# nRF7002-DK.net
KiCad netlist of a schematic drawn in Altium Designer
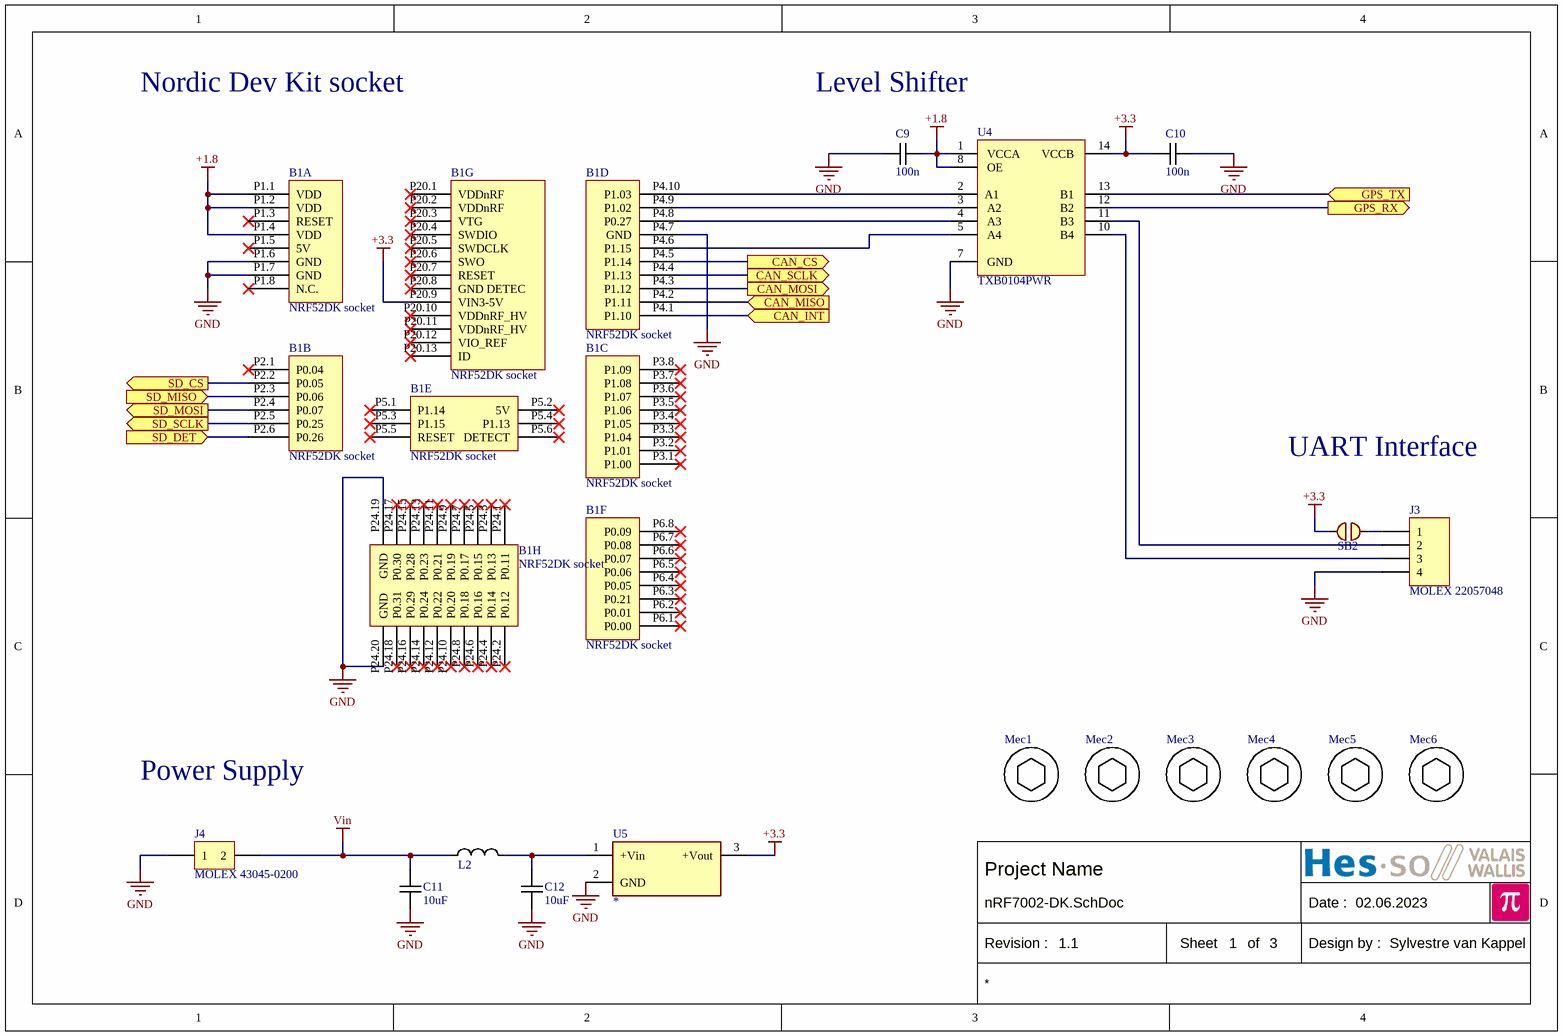
[diagram p0: nRF7002-DK.SchDoc]

(export (version "E")
  (design (tool "Eeschema 10.0.6"))
  (components
    (comp (ref "B1")
      (value "NRF52DK socket")
      (footprint "nRF5340DK SOCKET")
      (description "nRF53 development kit")
      (libsource (lib "") (part "nRF5340DK Socket_1"))
    )
    (comp (ref "C9")
      (value "100n")
      (footprint "CAPACITOR 1608 REFLOW")
      (description "Capacitor")
      (libsource (lib "Capacitor") (part "Capacitor"))
    )
    (comp (ref "C10")
      (value "100n")
      (footprint "CAPACITOR 1608 REFLOW")
      (description "Capacitor")
      (libsource (lib "Capacitor") (part "Capacitor"))
    )
    (comp (ref "C11")
      (value "10uF")
      (footprint "CAPACITOR 3216 REFLOW")
      (description "Capacitor")
      (libsource (lib "Capacitor") (part "Capacitor"))
    )
    (comp (ref "C12")
      (value "10uF")
      (footprint "CAPACITOR 3216 REFLOW")
      (description "Capacitor")
      (libsource (lib "Capacitor") (part "Capacitor"))
    )
    (comp (ref "J3")
      (value "MOLEX 22057048")
      (footprint "MOLEX 22057048")
      (description "KK 254 Wire-to-Board Header, Right-Angle, 4 Circuits")
      (libsource (lib "Connector") (part "MOLEX 22057048"))
    )
    (comp (ref "J4")
      (value "MOLEX 43045-0200")
      (footprint "MOLEX 43045-0200")
      (description "Micro-Fit 3.0 Right-Angle Header, 3.00mm, Dual Row, 2 Circuits")
      (libsource (lib "Connector") (part "MOLEX 43045-0200"))
    )
    (comp (ref "L2")
      (value "*")
      (footprint "TCK141")
      (description "Inductor")
      (libsource (lib "Inductor") (part "Inductor"))
    )
    (comp (ref "Mec1")
      (value "~")
      (footprint "Screw Hex Socket M3X5 Unconnected")
      (description "Screw Hex Socket Unconnected BN610")
      (libsource (lib "Mechanic") (part "Screw Hex Socket Unconnected"))
    )
    (comp (ref "Mec2")
      (value "~")
      (footprint "Screw Hex Socket M3X5 Unconnected")
      (description "Screw Hex Socket Unconnected BN610")
      (libsource (lib "Mechanic") (part "Screw Hex Socket Unconnected"))
    )
    (comp (ref "Mec3")
      (value "~")
      (footprint "Screw Hex Socket M3X5 Unconnected")
      (description "Screw Hex Socket Unconnected BN610")
      (libsource (lib "Mechanic") (part "Screw Hex Socket Unconnected"))
    )
    (comp (ref "Mec4")
      (value "~")
      (footprint "Screw Hex Socket M3X5 Unconnected")
      (description "Screw Hex Socket Unconnected BN610")
      (libsource (lib "Mechanic") (part "Screw Hex Socket Unconnected"))
    )
    (comp (ref "Mec5")
      (value "~")
      (footprint "Screw Hex Socket M3X5 Unconnected")
      (description "Screw Hex Socket Unconnected BN610")
      (libsource (lib "Mechanic") (part "Screw Hex Socket Unconnected"))
    )
    (comp (ref "Mec6")
      (value "~")
      (footprint "Screw Hex Socket M3X5 Unconnected")
      (description "Screw Hex Socket Unconnected BN610")
      (libsource (lib "Mechanic") (part "Screw Hex Socket Unconnected"))
    )
    (comp (ref "SB2")
      (value "*")
      (footprint "Solder Bridge 1mm Unconnected")
      (description "Solderbridge Unconnected")
      (libsource (lib "Jumper") (part "Solderbridge Unconnected"))
    )
    (comp (ref "U4")
      (value "TXB0104PWR")
      (footprint "TSSOP14 P0.65 C4.4x5.0 H1.1")
      (libsource (lib "IntegratedCircuit") (part "TXB0104PWR"))
    )
    (comp (ref "U5")
      (value "*")
      (footprint "TRACO TSR 1")
      (description "DC/DC Converter")
      (libsource (lib "VoltageConverter") (part "TRACO TSR 1"))
    )
  )
  (nets
    (net (code "1") (name "+1.8") (class "Default")
      (node (ref "B1") (pin "P1.1") (pinfunction "VDD_P1.1") (pintype "passive"))
      (node (ref "B1") (pin "P1.2") (pinfunction "VDD_P1.2") (pintype "passive"))
      (node (ref "B1") (pin "P1.4") (pinfunction "VDD_P1.4") (pintype "passive"))
      (node (ref "C9") (pin "1") (pinfunction "1_1") (pintype "passive"))
      (node (ref "U4") (pin "1") (pinfunction "VCCA_1") (pintype "passive"))
      (node (ref "U4") (pin "8") (pinfunction "OE_8") (pintype "passive"))
    )
    (net (code "2") (name "+3.3") (class "Default")
      (node (ref "B1") (pin "P20.9") (pinfunction "VIN3-5V_P20.9") (pintype "passive"))
      (node (ref "C10") (pin "2") (pinfunction "2_2") (pintype "passive"))
      (node (ref "SB2") (pin "2") (pinfunction "1_2") (pintype "passive"))
      (node (ref "U4") (pin "14") (pinfunction "VCCB_14") (pintype "passive"))
      (node (ref "U5") (pin "3") (pinfunction "+Vout_3") (pintype "passive"))
    )
    (net (code "3") (name "/CAN_CS") (class "Default")
      (node (ref "B1") (pin "P4.5") (pinfunction "P1.14_P4.5") (pintype "passive"))
    )
    (net (code "4") (name "/CAN_INT") (class "Default")
      (node (ref "B1") (pin "P4.1") (pinfunction "P1.10_P4.1") (pintype "passive"))
    )
    (net (code "5") (name "/CAN_MISO") (class "Default")
      (node (ref "B1") (pin "P4.2") (pinfunction "P1.11_P4.2") (pintype "passive"))
    )
    (net (code "6") (name "/CAN_MOSI") (class "Default")
      (node (ref "B1") (pin "P4.3") (pinfunction "P1.12_P4.3") (pintype "passive"))
    )
    (net (code "7") (name "/CAN_SCLK") (class "Default")
      (node (ref "B1") (pin "P4.4") (pinfunction "P1.13_P4.4") (pintype "passive"))
    )
    (net (code "8") (name "/GPS_RX") (class "Default")
      (node (ref "U4") (pin "12") (pinfunction "B2_12") (pintype "passive"))
    )
    (net (code "9") (name "/GPS_TX") (class "Default")
      (node (ref "U4") (pin "13") (pinfunction "B1_13") (pintype "passive"))
    )
    (net (code "10") (name "/SD_CS") (class "Default")
      (node (ref "B1") (pin "P2.2") (pinfunction "P0.05_P2.2") (pintype "passive"))
    )
    (net (code "11") (name "/SD_DET") (class "Default")
      (node (ref "B1") (pin "P2.6") (pinfunction "P0.26_P2.6") (pintype "passive"))
    )
    (net (code "12") (name "/SD_MISO") (class "Default")
      (node (ref "B1") (pin "P2.3") (pinfunction "P0.06_P2.3") (pintype "passive"))
    )
    (net (code "13") (name "/SD_MOSI") (class "Default")
      (node (ref "B1") (pin "P2.4") (pinfunction "P0.07_P2.4") (pintype "passive"))
    )
    (net (code "14") (name "/SD_SCLK") (class "Default")
      (node (ref "B1") (pin "P2.5") (pinfunction "P0.25_P2.5") (pintype "passive"))
    )
    (net (code "15") (name "GND") (class "Default")
      (node (ref "B1") (pin "P1.6") (pinfunction "GND_P1.6") (pintype "passive"))
      (node (ref "B1") (pin "P1.7") (pinfunction "GND_P1.7") (pintype "passive"))
      (node (ref "B1") (pin "P24.19") (pinfunction "GND_P24.19") (pintype "passive"))
      (node (ref "B1") (pin "P24.20") (pinfunction "GND_P24.20") (pintype "passive"))
      (node (ref "B1") (pin "P4.7") (pinfunction "GND_P4.7") (pintype "passive"))
      (node (ref "C10") (pin "1") (pinfunction "1_1") (pintype "passive"))
      (node (ref "C11") (pin "2") (pinfunction "2_2") (pintype "passive"))
      (node (ref "C12") (pin "2") (pinfunction "2_2") (pintype "passive"))
      (node (ref "C9") (pin "2") (pinfunction "2_2") (pintype "passive"))
      (node (ref "J3") (pin "4") (pinfunction "4_4") (pintype "passive"))
      (node (ref "J4") (pin "1") (pinfunction "1_1") (pintype "passive"))
      (node (ref "U4") (pin "7") (pinfunction "GND_7") (pintype "passive"))
      (node (ref "U5") (pin "2") (pinfunction "GND_2") (pintype "passive"))
    )
    (net (code "16") (name "Net-(B1D-P0.27)") (class "Default")
      (node (ref "B1") (pin "P4.8") (pinfunction "P0.27_P4.8") (pintype "passive"))
      (node (ref "U4") (pin "4") (pinfunction "A3_4") (pintype "passive"))
    )
    (net (code "17") (name "Net-(B1D-P1.02)") (class "Default")
      (node (ref "B1") (pin "P4.9") (pinfunction "P1.02_P4.9") (pintype "passive"))
      (node (ref "U4") (pin "3") (pinfunction "A2_3") (pintype "passive"))
    )
    (net (code "18") (name "Net-(B1D-P1.03)") (class "Default")
      (node (ref "B1") (pin "P4.10") (pinfunction "P1.03_P4.10") (pintype "passive"))
      (node (ref "U4") (pin "2") (pinfunction "A1_2") (pintype "passive"))
    )
    (net (code "19") (name "Net-(B1D-P1.15)") (class "Default")
      (node (ref "B1") (pin "P4.6") (pinfunction "P1.15_P4.6") (pintype "passive"))
      (node (ref "U4") (pin "5") (pinfunction "A4_5") (pintype "passive"))
    )
    (net (code "20") (name "Net-(SB2-0)") (class "Default")
      (node (ref "J3") (pin "1") (pinfunction "1_1") (pintype "passive"))
      (node (ref "SB2") (pin "1") (pinfunction "0_1") (pintype "passive"))
    )
    (net (code "21") (name "Net-(U4-B3)") (class "Default")
      (node (ref "J3") (pin "2") (pinfunction "2_2") (pintype "passive"))
      (node (ref "U4") (pin "11") (pinfunction "B3_11") (pintype "passive"))
    )
    (net (code "22") (name "Net-(U4-B4)") (class "Default")
      (node (ref "J3") (pin "3") (pinfunction "3_3") (pintype "passive"))
      (node (ref "U4") (pin "10") (pinfunction "B4_10") (pintype "passive"))
    )
    (net (code "23") (name "Net-(U5-+Vin)") (class "Default")
      (node (ref "C12") (pin "1") (pinfunction "1_1") (pintype "passive"))
      (node (ref "L2") (pin "2") (pinfunction "2_2") (pintype "passive"))
      (node (ref "U5") (pin "1") (pinfunction "+Vin_1") (pintype "passive"))
    )
    (net (code "24") (name "Vin") (class "Default")
      (node (ref "C11") (pin "1") (pinfunction "1_1") (pintype "passive"))
      (node (ref "J4") (pin "2") (pinfunction "2_2") (pintype "passive"))
      (node (ref "L2") (pin "1") (pinfunction "1_1") (pintype "passive"))
    )
    (net (code "25") (name "unconnected-(B1A-5V-PadP1.5)") (class "Default")
      (node (ref "B1") (pin "P1.5") (pinfunction "5V_P1.5") (pintype "passive+no_connect"))
    )
    (net (code "26") (name "unconnected-(B1A-N.C.-PadP1.8)") (class "Default")
      (node (ref "B1") (pin "P1.8") (pinfunction "N.C._P1.8") (pintype "passive+no_connect"))
    )
    (net (code "27") (name "unconnected-(B1A-RESET-PadP1.3)") (class "Default")
      (node (ref "B1") (pin "P1.3") (pinfunction "RESET_P1.3") (pintype "passive+no_connect"))
    )
    (net (code "28") (name "unconnected-(B1B-P0.04-PadP2.1)") (class "Default")
      (node (ref "B1") (pin "P2.1") (pinfunction "P0.04_P2.1") (pintype "passive+no_connect"))
    )
    (net (code "29") (name "unconnected-(B1C-P1.00-PadP3.1)") (class "Default")
      (node (ref "B1") (pin "P3.1") (pinfunction "P1.00_P3.1") (pintype "passive+no_connect"))
    )
    (net (code "30") (name "unconnected-(B1C-P1.01-PadP3.2)") (class "Default")
      (node (ref "B1") (pin "P3.2") (pinfunction "P1.01_P3.2") (pintype "passive+no_connect"))
    )
    (net (code "31") (name "unconnected-(B1C-P1.04-PadP3.3)") (class "Default")
      (node (ref "B1") (pin "P3.3") (pinfunction "P1.04_P3.3") (pintype "passive+no_connect"))
    )
    (net (code "32") (name "unconnected-(B1C-P1.05-PadP3.4)") (class "Default")
      (node (ref "B1") (pin "P3.4") (pinfunction "P1.05_P3.4") (pintype "passive+no_connect"))
    )
    (net (code "33") (name "unconnected-(B1C-P1.06-PadP3.5)") (class "Default")
      (node (ref "B1") (pin "P3.5") (pinfunction "P1.06_P3.5") (pintype "passive+no_connect"))
    )
    (net (code "34") (name "unconnected-(B1C-P1.07-PadP3.6)") (class "Default")
      (node (ref "B1") (pin "P3.6") (pinfunction "P1.07_P3.6") (pintype "passive+no_connect"))
    )
    (net (code "35") (name "unconnected-(B1C-P1.08-PadP3.7)") (class "Default")
      (node (ref "B1") (pin "P3.7") (pinfunction "P1.08_P3.7") (pintype "passive+no_connect"))
    )
    (net (code "36") (name "unconnected-(B1C-P1.09-PadP3.8)") (class "Default")
      (node (ref "B1") (pin "P3.8") (pinfunction "P1.09_P3.8") (pintype "passive+no_connect"))
    )
    (net (code "37") (name "unconnected-(B1E-5V-PadP5.2)") (class "Default")
      (node (ref "B1") (pin "P5.2") (pinfunction "5V_P5.2") (pintype "passive+no_connect"))
    )
    (net (code "38") (name "unconnected-(B1E-DETECT-PadP5.6)") (class "Default")
      (node (ref "B1") (pin "P5.6") (pinfunction "DETECT_P5.6") (pintype "passive+no_connect"))
    )
    (net (code "39") (name "unconnected-(B1E-P1.13-PadP5.4)") (class "Default")
      (node (ref "B1") (pin "P5.4") (pinfunction "P1.13_P5.4") (pintype "passive+no_connect"))
    )
    (net (code "40") (name "unconnected-(B1E-P1.14-PadP5.1)") (class "Default")
      (node (ref "B1") (pin "P5.1") (pinfunction "P1.14_P5.1") (pintype "passive+no_connect"))
    )
    (net (code "41") (name "unconnected-(B1E-P1.15-PadP5.3)") (class "Default")
      (node (ref "B1") (pin "P5.3") (pinfunction "P1.15_P5.3") (pintype "passive+no_connect"))
    )
    (net (code "42") (name "unconnected-(B1E-RESET-PadP5.5)") (class "Default")
      (node (ref "B1") (pin "P5.5") (pinfunction "RESET_P5.5") (pintype "passive+no_connect"))
    )
    (net (code "43") (name "unconnected-(B1F-P0.00-PadP6.1)") (class "Default")
      (node (ref "B1") (pin "P6.1") (pinfunction "P0.00_P6.1") (pintype "passive+no_connect"))
    )
    (net (code "44") (name "unconnected-(B1F-P0.01-PadP6.2)") (class "Default")
      (node (ref "B1") (pin "P6.2") (pinfunction "P0.01_P6.2") (pintype "passive+no_connect"))
    )
    (net (code "45") (name "unconnected-(B1F-P0.05-PadP6.4)") (class "Default")
      (node (ref "B1") (pin "P6.4") (pinfunction "P0.05_P6.4") (pintype "passive+no_connect"))
    )
    (net (code "46") (name "unconnected-(B1F-P0.06-PadP6.5)") (class "Default")
      (node (ref "B1") (pin "P6.5") (pinfunction "P0.06_P6.5") (pintype "passive+no_connect"))
    )
    (net (code "47") (name "unconnected-(B1F-P0.07-PadP6.6)") (class "Default")
      (node (ref "B1") (pin "P6.6") (pinfunction "P0.07_P6.6") (pintype "passive+no_connect"))
    )
    (net (code "48") (name "unconnected-(B1F-P0.08-PadP6.7)") (class "Default")
      (node (ref "B1") (pin "P6.7") (pinfunction "P0.08_P6.7") (pintype "passive+no_connect"))
    )
    (net (code "49") (name "unconnected-(B1F-P0.09-PadP6.8)") (class "Default")
      (node (ref "B1") (pin "P6.8") (pinfunction "P0.09_P6.8") (pintype "passive+no_connect"))
    )
    (net (code "50") (name "unconnected-(B1F-P0.21-PadP6.3)") (class "Default")
      (node (ref "B1") (pin "P6.3") (pinfunction "P0.21_P6.3") (pintype "passive+no_connect"))
    )
    (net (code "51") (name "unconnected-(B1G-GND_DETEC-PadP20.8)") (class "Default")
      (node (ref "B1") (pin "P20.8") (pinfunction "GND_DETEC_P20.8") (pintype "passive+no_connect"))
    )
    (net (code "52") (name "unconnected-(B1G-ID-PadP20.13)") (class "Default")
      (node (ref "B1") (pin "P20.13") (pinfunction "ID_P20.13") (pintype "passive+no_connect"))
    )
    (net (code "53") (name "unconnected-(B1G-RESET-PadP20.7)") (class "Default")
      (node (ref "B1") (pin "P20.7") (pinfunction "RESET_P20.7") (pintype "passive+no_connect"))
    )
    (net (code "54") (name "unconnected-(B1G-SWDCLK-PadP20.5)") (class "Default")
      (node (ref "B1") (pin "P20.5") (pinfunction "SWDCLK_P20.5") (pintype "passive+no_connect"))
    )
    (net (code "55") (name "unconnected-(B1G-SWDIO-PadP20.4)") (class "Default")
      (node (ref "B1") (pin "P20.4") (pinfunction "SWDIO_P20.4") (pintype "passive+no_connect"))
    )
    (net (code "56") (name "unconnected-(B1G-SWO-PadP20.6)") (class "Default")
      (node (ref "B1") (pin "P20.6") (pinfunction "SWO_P20.6") (pintype "passive+no_connect"))
    )
    (net (code "57") (name "unconnected-(B1G-VDDnRF-PadP20.1)") (class "Default")
      (node (ref "B1") (pin "P20.1") (pinfunction "VDDnRF_P20.1") (pintype "passive+no_connect"))
    )
    (net (code "58") (name "unconnected-(B1G-VDDnRF-PadP20.2)") (class "Default")
      (node (ref "B1") (pin "P20.2") (pinfunction "VDDnRF_P20.2") (pintype "passive+no_connect"))
    )
    (net (code "59") (name "unconnected-(B1G-VDDnRF_HV-PadP20.10)") (class "Default")
      (node (ref "B1") (pin "P20.10") (pinfunction "VDDnRF_HV_P20.10") (pintype "passive+no_connect"))
    )
    (net (code "60") (name "unconnected-(B1G-VDDnRF_HV-PadP20.11)") (class "Default")
      (node (ref "B1") (pin "P20.11") (pinfunction "VDDnRF_HV_P20.11") (pintype "passive+no_connect"))
    )
    (net (code "61") (name "unconnected-(B1G-VIO_REF-PadP20.12)") (class "Default")
      (node (ref "B1") (pin "P20.12") (pinfunction "VIO_REF_P20.12") (pintype "passive+no_connect"))
    )
    (net (code "62") (name "unconnected-(B1G-VTG-PadP20.3)") (class "Default")
      (node (ref "B1") (pin "P20.3") (pinfunction "VTG_P20.3") (pintype "passive+no_connect"))
    )
    (net (code "63") (name "unconnected-(B1H-P0.11-PadP24.1)") (class "Default")
      (node (ref "B1") (pin "P24.1") (pinfunction "P0.11_P24.1") (pintype "passive+no_connect"))
    )
    (net (code "64") (name "unconnected-(B1H-P0.12-PadP24.2)") (class "Default")
      (node (ref "B1") (pin "P24.2") (pinfunction "P0.12_P24.2") (pintype "passive+no_connect"))
    )
    (net (code "65") (name "unconnected-(B1H-P0.13-PadP24.3)") (class "Default")
      (node (ref "B1") (pin "P24.3") (pinfunction "P0.13_P24.3") (pintype "passive+no_connect"))
    )
    (net (code "66") (name "unconnected-(B1H-P0.14-PadP24.4)") (class "Default")
      (node (ref "B1") (pin "P24.4") (pinfunction "P0.14_P24.4") (pintype "passive+no_connect"))
    )
    (net (code "67") (name "unconnected-(B1H-P0.15-PadP24.5)") (class "Default")
      (node (ref "B1") (pin "P24.5") (pinfunction "P0.15_P24.5") (pintype "passive+no_connect"))
    )
    (net (code "68") (name "unconnected-(B1H-P0.16-PadP24.6)") (class "Default")
      (node (ref "B1") (pin "P24.6") (pinfunction "P0.16_P24.6") (pintype "passive+no_connect"))
    )
    (net (code "69") (name "unconnected-(B1H-P0.17-PadP24.7)") (class "Default")
      (node (ref "B1") (pin "P24.7") (pinfunction "P0.17_P24.7") (pintype "passive+no_connect"))
    )
    (net (code "70") (name "unconnected-(B1H-P0.18-PadP24.8)") (class "Default")
      (node (ref "B1") (pin "P24.8") (pinfunction "P0.18_P24.8") (pintype "passive+no_connect"))
    )
    (net (code "71") (name "unconnected-(B1H-P0.19-PadP24.9)") (class "Default")
      (node (ref "B1") (pin "P24.9") (pinfunction "P0.19_P24.9") (pintype "passive+no_connect"))
    )
    (net (code "72") (name "unconnected-(B1H-P0.20-PadP24.10)") (class "Default")
      (node (ref "B1") (pin "P24.10") (pinfunction "P0.20_P24.10") (pintype "passive+no_connect"))
    )
    (net (code "73") (name "unconnected-(B1H-P0.21-PadP24.11)") (class "Default")
      (node (ref "B1") (pin "P24.11") (pinfunction "P0.21_P24.11") (pintype "passive+no_connect"))
    )
    (net (code "74") (name "unconnected-(B1H-P0.22-PadP24.12)") (class "Default")
      (node (ref "B1") (pin "P24.12") (pinfunction "P0.22_P24.12") (pintype "passive+no_connect"))
    )
    (net (code "75") (name "unconnected-(B1H-P0.23-PadP24.13)") (class "Default")
      (node (ref "B1") (pin "P24.13") (pinfunction "P0.23_P24.13") (pintype "passive+no_connect"))
    )
    (net (code "76") (name "unconnected-(B1H-P0.24-PadP24.14)") (class "Default")
      (node (ref "B1") (pin "P24.14") (pinfunction "P0.24_P24.14") (pintype "passive+no_connect"))
    )
    (net (code "77") (name "unconnected-(B1H-P0.28-PadP24.15)") (class "Default")
      (node (ref "B1") (pin "P24.15") (pinfunction "P0.28_P24.15") (pintype "passive+no_connect"))
    )
    (net (code "78") (name "unconnected-(B1H-P0.29-PadP24.16)") (class "Default")
      (node (ref "B1") (pin "P24.16") (pinfunction "P0.29_P24.16") (pintype "passive+no_connect"))
    )
    (net (code "79") (name "unconnected-(B1H-P0.30-PadP24.17)") (class "Default")
      (node (ref "B1") (pin "P24.17") (pinfunction "P0.30_P24.17") (pintype "passive+no_connect"))
    )
    (net (code "80") (name "unconnected-(B1H-P0.31-PadP24.18)") (class "Default")
      (node (ref "B1") (pin "P24.18") (pinfunction "P0.31_P24.18") (pintype "passive+no_connect"))
    )
  )
)
